# ChessPCB.net
KiCad netlist of a schematic drawn in EAGLE
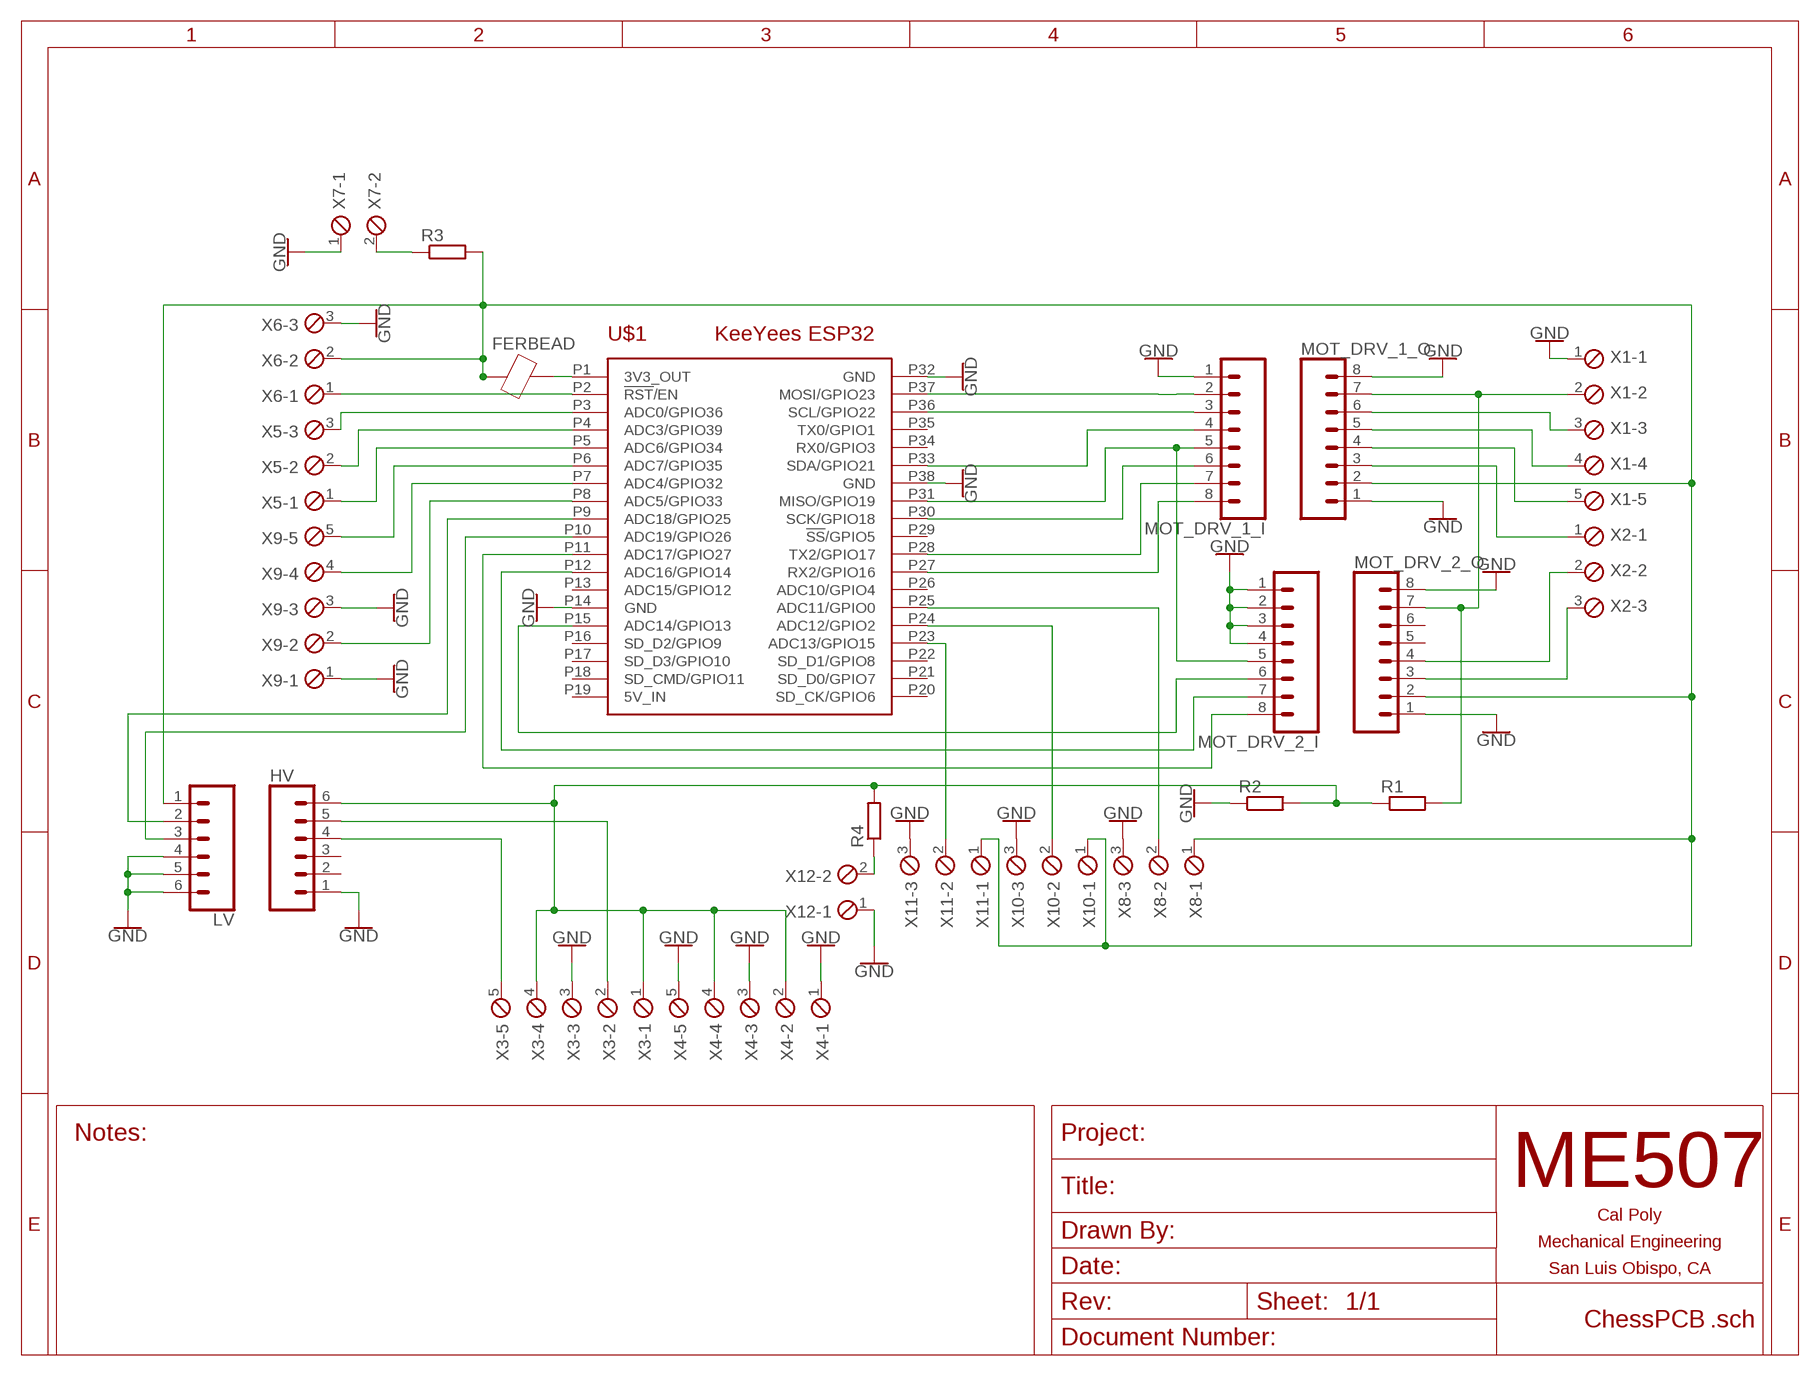
[diagram p0: schematic, sheet 1]

(export (version "E")
  (design (tool "Eeschema 10.0.6"))
  (components
    (comp (ref "FERBEAD")
      (value "BEAD0402")
      (footprint "eagle-import:0402")
      (libsource (lib "eagle-import") (part "BEAD0402"))
    )
    (comp (ref "HV")
      (value "CONN_06SILK_FEMALE_PTH")
      (footprint "eagle-import:1X06")
      (libsource (lib "eagle-import") (part "CONN_06SILK_FEMALE_PTH"))
    )
    (comp (ref "LV")
      (value "CONN_06SILK_FEMALE_PTH")
      (footprint "eagle-import:1X06")
      (libsource (lib "eagle-import") (part "CONN_06SILK_FEMALE_PTH"))
    )
    (comp (ref "MOT_DRV_1_I")
      (value "CONN_08\"")
      (footprint "eagle-import:1X08")
      (libsource (lib "eagle-import") (part "CONN_08{dblquote}"))
    )
    (comp (ref "MOT_DRV_1_O")
      (value "CONN_08\"")
      (footprint "eagle-import:1X08")
      (libsource (lib "eagle-import") (part "CONN_08{dblquote}"))
    )
    (comp (ref "MOT_DRV_2_I")
      (value "CONN_08\"")
      (footprint "eagle-import:1X08")
      (libsource (lib "eagle-import") (part "CONN_08{dblquote}"))
    )
    (comp (ref "MOT_DRV_2_O")
      (value "CONN_08\"")
      (footprint "eagle-import:1X08")
      (libsource (lib "eagle-import") (part "CONN_08{dblquote}"))
    )
    (comp (ref "R1")
      (value "R-EU_0204/7")
      (footprint "eagle-import:0204_7")
      (libsource (lib "eagle-import") (part "R-EU_0204/7"))
    )
    (comp (ref "R2")
      (value "R-EU_0204/7")
      (footprint "eagle-import:0204_7")
      (libsource (lib "eagle-import") (part "R-EU_0204/7"))
    )
    (comp (ref "R3")
      (value "R-EU_0204/7")
      (footprint "eagle-import:0204_7")
      (libsource (lib "eagle-import") (part "R-EU_0204/7"))
    )
    (comp (ref "R4")
      (value "R-EU_0204/7")
      (footprint "eagle-import:0204_7")
      (libsource (lib "eagle-import") (part "R-EU_0204/7"))
    )
    (comp (ref "U$1")
      (value "KEEYEES_ESP32")
      (footprint "eagle-import:KEEYEES_ESP32")
      (libsource (lib "eagle-import") (part "KEEYEES_ESP32"))
    )
    (comp (ref "X1")
      (value "SCREWTERM_5P_254")
      (footprint "eagle-import:5POL254")
      (libsource (lib "eagle-import") (part "SCREWTERM_5P_254"))
    )
    (comp (ref "X2")
      (value "SCREWTERM_3P_254")
      (footprint "eagle-import:3POL254")
      (libsource (lib "eagle-import") (part "SCREWTERM_3P_254"))
    )
    (comp (ref "X3")
      (value "SCREWTERM_5P_254")
      (footprint "eagle-import:5POL254")
      (libsource (lib "eagle-import") (part "SCREWTERM_5P_254"))
    )
    (comp (ref "X4")
      (value "SCREWTERM_5P_254")
      (footprint "eagle-import:5POL254")
      (libsource (lib "eagle-import") (part "SCREWTERM_5P_254"))
    )
    (comp (ref "X5")
      (value "SCREWTERM_3P_254")
      (footprint "eagle-import:3POL254")
      (libsource (lib "eagle-import") (part "SCREWTERM_3P_254"))
    )
    (comp (ref "X6")
      (value "SCREWTERM_3P_254")
      (footprint "eagle-import:3POL254")
      (libsource (lib "eagle-import") (part "SCREWTERM_3P_254"))
    )
    (comp (ref "X7")
      (value "SCREWTERM_2P_254")
      (footprint "eagle-import:2POL254")
      (libsource (lib "eagle-import") (part "SCREWTERM_2P_254"))
    )
    (comp (ref "X8")
      (value "SCREWTERM_3P_254")
      (footprint "eagle-import:3POL254")
      (libsource (lib "eagle-import") (part "SCREWTERM_3P_254"))
    )
    (comp (ref "X9")
      (value "SCREWTERM_5P_254")
      (footprint "eagle-import:5POL254")
      (libsource (lib "eagle-import") (part "SCREWTERM_5P_254"))
    )
    (comp (ref "X10")
      (value "SCREWTERM_3P_254")
      (footprint "eagle-import:3POL254")
      (libsource (lib "eagle-import") (part "SCREWTERM_3P_254"))
    )
    (comp (ref "X11")
      (value "SCREWTERM_3P_254")
      (footprint "eagle-import:3POL254")
      (libsource (lib "eagle-import") (part "SCREWTERM_3P_254"))
    )
    (comp (ref "X12")
      (value "SCREWTERM_2P_254")
      (footprint "eagle-import:2POL254")
      (libsource (lib "eagle-import") (part "SCREWTERM_2P_254"))
    )
  )
  (nets
    (net (code "1") (name "/5V_IN") (class "Default")
      (node (ref "U$1") (pin "P19") (pinfunction "5V_IN_P19") (pintype "power_in"))
    )
    (net (code "2") (name "GND") (class "Default")
      (node (ref "HV") (pin "1") (pinfunction "1_1") (pintype "passive"))
      (node (ref "LV") (pin "4") (pinfunction "4_4") (pintype "passive"))
      (node (ref "LV") (pin "5") (pinfunction "5_5") (pintype "passive"))
      (node (ref "LV") (pin "6") (pinfunction "6_6") (pintype "passive"))
      (node (ref "MOT_DRV_1_I") (pin "1") (pinfunction "1_1") (pintype "passive"))
      (node (ref "MOT_DRV_1_O") (pin "1") (pinfunction "1_1") (pintype "passive"))
      (node (ref "MOT_DRV_1_O") (pin "8") (pinfunction "8_8") (pintype "passive"))
      (node (ref "MOT_DRV_2_I") (pin "1") (pinfunction "1_1") (pintype "passive"))
      (node (ref "MOT_DRV_2_I") (pin "2") (pinfunction "2_2") (pintype "passive"))
      (node (ref "MOT_DRV_2_I") (pin "3") (pinfunction "3_3") (pintype "passive"))
      (node (ref "MOT_DRV_2_I") (pin "4") (pinfunction "4_4") (pintype "passive"))
      (node (ref "MOT_DRV_2_O") (pin "1") (pinfunction "1_1") (pintype "passive"))
      (node (ref "MOT_DRV_2_O") (pin "8") (pinfunction "8_8") (pintype "passive"))
      (node (ref "R2") (pin "1") (pinfunction "1_1") (pintype "passive"))
      (node (ref "U$1") (pin "P14") (pinfunction "GND_P14") (pintype "power_in"))
      (node (ref "U$1") (pin "P32") (pinfunction "GND_P32") (pintype "power_in"))
      (node (ref "U$1") (pin "P38") (pinfunction "GND_P38") (pintype "power_in"))
      (node (ref "X1") (pin "1") (pinfunction "1_1") (pintype "passive"))
      (node (ref "X10") (pin "3") (pinfunction "1_3") (pintype "passive"))
      (node (ref "X11") (pin "3") (pinfunction "1_3") (pintype "passive"))
      (node (ref "X12") (pin "1") (pinfunction "1_1") (pintype "passive"))
      (node (ref "X3") (pin "3") (pinfunction "1_3") (pintype "passive"))
      (node (ref "X4") (pin "1") (pinfunction "1_1") (pintype "passive"))
      (node (ref "X4") (pin "3") (pinfunction "1_3") (pintype "passive"))
      (node (ref "X4") (pin "5") (pinfunction "1_5") (pintype "passive"))
      (node (ref "X6") (pin "3") (pinfunction "1_3") (pintype "passive"))
      (node (ref "X7") (pin "1") (pinfunction "1_1") (pintype "passive"))
      (node (ref "X8") (pin "3") (pinfunction "1_3") (pintype "passive"))
      (node (ref "X9") (pin "1") (pinfunction "1_1") (pintype "passive"))
      (node (ref "X9") (pin "3") (pinfunction "1_3") (pintype "passive"))
    )
    (net (code "3") (name "Net-(MOT_DRV_1_O-Pad3)") (class "Default")
      (node (ref "MOT_DRV_1_O") (pin "3") (pinfunction "3_3") (pintype "passive"))
      (node (ref "X2") (pin "1") (pinfunction "1_1") (pintype "passive"))
    )
    (net (code "4") (name "Net-(U$1-3V3_OUT)") (class "Default")
      (node (ref "FERBEAD") (pin "2") (pinfunction "2_2") (pintype "bidirectional"))
      (node (ref "U$1") (pin "P1") (pinfunction "3V3_OUT_P1") (pintype "power_in"))
    )
    (net (code "5") (name "Net-(U$1-ADC0{slash}GPIO36)") (class "Default")
      (node (ref "U$1") (pin "P3") (pinfunction "ADC0/GPIO36_P3") (pintype "bidirectional"))
      (node (ref "X5") (pin "3") (pinfunction "1_3") (pintype "passive"))
    )
    (net (code "6") (name "Net-(U$1-ADC3{slash}GPIO39)") (class "Default")
      (node (ref "U$1") (pin "P4") (pinfunction "ADC3/GPIO39_P4") (pintype "bidirectional"))
      (node (ref "X5") (pin "2") (pinfunction "1_2") (pintype "passive"))
    )
    (net (code "7") (name "Net-(U$1-ADC4{slash}GPIO32)") (class "Default")
      (node (ref "U$1") (pin "P7") (pinfunction "ADC4/GPIO32_P7") (pintype "bidirectional"))
      (node (ref "X9") (pin "4") (pinfunction "1_4") (pintype "passive"))
    )
    (net (code "8") (name "Net-(U$1-ADC5{slash}GPIO33)") (class "Default")
      (node (ref "U$1") (pin "P8") (pinfunction "ADC5/GPIO33_P8") (pintype "bidirectional"))
      (node (ref "X9") (pin "2") (pinfunction "1_2") (pintype "passive"))
    )
    (net (code "9") (name "Net-(U$1-ADC6{slash}GPIO34)") (class "Default")
      (node (ref "U$1") (pin "P5") (pinfunction "ADC6/GPIO34_P5") (pintype "bidirectional"))
      (node (ref "X5") (pin "1") (pinfunction "1_1") (pintype "passive"))
    )
    (net (code "10") (name "Net-(U$1-ADC7{slash}GPIO35)") (class "Default")
      (node (ref "U$1") (pin "P6") (pinfunction "ADC7/GPIO35_P6") (pintype "bidirectional"))
      (node (ref "X9") (pin "5") (pinfunction "1_5") (pintype "passive"))
    )
    (net (code "11") (name "Net-(U$1-ADC11{slash}GPIO0)") (class "Default")
      (node (ref "U$1") (pin "P25") (pinfunction "ADC11/GPIO0_P25") (pintype "bidirectional"))
      (node (ref "X8") (pin "2") (pinfunction "1_2") (pintype "passive"))
    )
    (net (code "12") (name "Net-(U$1-ADC12{slash}GPIO2)") (class "Default")
      (node (ref "U$1") (pin "P24") (pinfunction "ADC12/GPIO2_P24") (pintype "bidirectional"))
      (node (ref "X10") (pin "2") (pinfunction "1_2") (pintype "passive"))
    )
    (net (code "13") (name "Net-(U$1-ADC13{slash}GPIO15)") (class "Default")
      (node (ref "U$1") (pin "P23") (pinfunction "ADC13/GPIO15_P23") (pintype "bidirectional"))
      (node (ref "X11") (pin "2") (pinfunction "1_2") (pintype "passive"))
    )
    (net (code "14") (name "Net-(U$1-ADC14{slash}GPIO13)") (class "Default")
      (node (ref "MOT_DRV_2_I") (pin "6") (pinfunction "6_6") (pintype "passive"))
      (node (ref "U$1") (pin "P15") (pinfunction "ADC14/GPIO13_P15") (pintype "bidirectional"))
    )
    (net (code "15") (name "Net-(U$1-ADC16{slash}GPIO14)") (class "Default")
      (node (ref "MOT_DRV_2_I") (pin "7") (pinfunction "7_7") (pintype "passive"))
      (node (ref "U$1") (pin "P12") (pinfunction "ADC16/GPIO14_P12") (pintype "bidirectional"))
    )
    (net (code "16") (name "Net-(U$1-ADC17{slash}GPIO27)") (class "Default")
      (node (ref "MOT_DRV_2_I") (pin "8") (pinfunction "8_8") (pintype "passive"))
      (node (ref "U$1") (pin "P11") (pinfunction "ADC17/GPIO27_P11") (pintype "bidirectional"))
    )
    (net (code "17") (name "Net-(U$1-ADC18{slash}GPIO25)") (class "Default")
      (node (ref "LV") (pin "2") (pinfunction "2_2") (pintype "passive"))
      (node (ref "U$1") (pin "P9") (pinfunction "ADC18/GPIO25_P9") (pintype "bidirectional"))
    )
    (net (code "18") (name "Net-(U$1-ADC19{slash}GPIO26)") (class "Default")
      (node (ref "LV") (pin "3") (pinfunction "3_3") (pintype "passive"))
      (node (ref "U$1") (pin "P10") (pinfunction "ADC19/GPIO26_P10") (pintype "bidirectional"))
    )
    (net (code "19") (name "Net-(U$1-MISO{slash}GPIO19)") (class "Default")
      (node (ref "MOT_DRV_1_I") (pin "5") (pinfunction "5_5") (pintype "passive"))
      (node (ref "MOT_DRV_2_I") (pin "5") (pinfunction "5_5") (pintype "passive"))
      (node (ref "U$1") (pin "P31") (pinfunction "MISO/GPIO19_P31") (pintype "bidirectional"))
    )
    (net (code "20") (name "Net-(U$1-MOSI{slash}GPIO23)") (class "Default")
      (node (ref "MOT_DRV_1_I") (pin "2") (pinfunction "2_2") (pintype "passive"))
      (node (ref "U$1") (pin "P37") (pinfunction "MOSI/GPIO23_P37") (pintype "bidirectional"))
    )
    (net (code "21") (name "Net-(U$1-RX2{slash}GPIO16)") (class "Default")
      (node (ref "MOT_DRV_1_I") (pin "8") (pinfunction "8_8") (pintype "passive"))
      (node (ref "U$1") (pin "P27") (pinfunction "RX2/GPIO16_P27") (pintype "bidirectional"))
    )
    (net (code "22") (name "Net-(U$1-SCK{slash}GPIO18)") (class "Default")
      (node (ref "MOT_DRV_1_I") (pin "6") (pinfunction "6_6") (pintype "passive"))
      (node (ref "U$1") (pin "P30") (pinfunction "SCK/GPIO18_P30") (pintype "bidirectional"))
    )
    (net (code "23") (name "Net-(U$1-SCL{slash}GPIO22)") (class "Default")
      (node (ref "MOT_DRV_1_I") (pin "3") (pinfunction "3_3") (pintype "passive"))
      (node (ref "U$1") (pin "P36") (pinfunction "SCL/GPIO22_P36") (pintype "bidirectional"))
    )
    (net (code "24") (name "Net-(U$1-SDA{slash}GPIO21)") (class "Default")
      (node (ref "MOT_DRV_1_I") (pin "4") (pinfunction "4_4") (pintype "passive"))
      (node (ref "U$1") (pin "P33") (pinfunction "SDA/GPIO21_P33") (pintype "bidirectional"))
    )
    (net (code "25") (name "Net-(U$1-TX2{slash}GPIO17)") (class "Default")
      (node (ref "MOT_DRV_1_I") (pin "7") (pinfunction "7_7") (pintype "passive"))
      (node (ref "U$1") (pin "P28") (pinfunction "TX2/GPIO17_P28") (pintype "bidirectional"))
    )
    (net (code "26") (name "Net-(U$1-~{RST}{slash}EN)") (class "Default")
      (node (ref "U$1") (pin "P2") (pinfunction "~{RST}/EN_P2") (pintype "input"))
      (node (ref "X6") (pin "1") (pinfunction "1_1") (pintype "passive"))
    )
    (net (code "27") (name "Net-(X1B-1)") (class "Default")
      (node (ref "MOT_DRV_1_O") (pin "7") (pinfunction "7_7") (pintype "passive"))
      (node (ref "MOT_DRV_2_O") (pin "7") (pinfunction "7_7") (pintype "passive"))
      (node (ref "R1") (pin "2") (pinfunction "2_2") (pintype "passive"))
      (node (ref "X1") (pin "2") (pinfunction "1_2") (pintype "passive"))
    )
    (net (code "28") (name "Net-(X1C-1)") (class "Default")
      (node (ref "MOT_DRV_1_O") (pin "6") (pinfunction "6_6") (pintype "passive"))
      (node (ref "X1") (pin "3") (pinfunction "1_3") (pintype "passive"))
    )
    (net (code "29") (name "Net-(X1D-1)") (class "Default")
      (node (ref "MOT_DRV_1_O") (pin "5") (pinfunction "5_5") (pintype "passive"))
      (node (ref "X1") (pin "4") (pinfunction "1_4") (pintype "passive"))
    )
    (net (code "30") (name "Net-(X1E-1)") (class "Default")
      (node (ref "MOT_DRV_1_O") (pin "4") (pinfunction "4_4") (pintype "passive"))
      (node (ref "X1") (pin "5") (pinfunction "1_5") (pintype "passive"))
    )
    (net (code "31") (name "Net-(X2B-1)") (class "Default")
      (node (ref "MOT_DRV_2_O") (pin "4") (pinfunction "4_4") (pintype "passive"))
      (node (ref "X2") (pin "2") (pinfunction "1_2") (pintype "passive"))
    )
    (net (code "32") (name "Net-(X2C-1)") (class "Default")
      (node (ref "MOT_DRV_2_O") (pin "3") (pinfunction "3_3") (pintype "passive"))
      (node (ref "X2") (pin "3") (pinfunction "1_3") (pintype "passive"))
    )
    (net (code "33") (name "Net-(X3B-1)") (class "Default")
      (node (ref "HV") (pin "5") (pinfunction "5_5") (pintype "passive"))
      (node (ref "X3") (pin "2") (pinfunction "1_2") (pintype "passive"))
    )
    (net (code "34") (name "Net-(X3D-1)") (class "Default")
      (node (ref "HV") (pin "6") (pinfunction "6_6") (pintype "passive"))
      (node (ref "R1") (pin "1") (pinfunction "1_1") (pintype "passive"))
      (node (ref "R2") (pin "2") (pinfunction "2_2") (pintype "passive"))
      (node (ref "R4") (pin "2") (pinfunction "2_2") (pintype "passive"))
      (node (ref "X3") (pin "1") (pinfunction "1_1") (pintype "passive"))
      (node (ref "X3") (pin "4") (pinfunction "1_4") (pintype "passive"))
      (node (ref "X4") (pin "2") (pinfunction "1_2") (pintype "passive"))
      (node (ref "X4") (pin "4") (pinfunction "1_4") (pintype "passive"))
    )
    (net (code "35") (name "Net-(X3E-1)") (class "Default")
      (node (ref "HV") (pin "4") (pinfunction "4_4") (pintype "passive"))
      (node (ref "X3") (pin "5") (pinfunction "1_5") (pintype "passive"))
    )
    (net (code "36") (name "Net-(X6B-1)") (class "Default")
      (node (ref "FERBEAD") (pin "1") (pinfunction "1_1") (pintype "bidirectional"))
      (node (ref "LV") (pin "1") (pinfunction "1_1") (pintype "passive"))
      (node (ref "MOT_DRV_1_O") (pin "2") (pinfunction "2_2") (pintype "passive"))
      (node (ref "MOT_DRV_2_O") (pin "2") (pinfunction "2_2") (pintype "passive"))
      (node (ref "R3") (pin "2") (pinfunction "2_2") (pintype "passive"))
      (node (ref "X10") (pin "1") (pinfunction "1_1") (pintype "passive"))
      (node (ref "X11") (pin "1") (pinfunction "1_1") (pintype "passive"))
      (node (ref "X6") (pin "2") (pinfunction "1_2") (pintype "passive"))
      (node (ref "X8") (pin "1") (pinfunction "1_1") (pintype "passive"))
    )
    (net (code "37") (name "Net-(X7B-1)") (class "Default")
      (node (ref "R3") (pin "1") (pinfunction "1_1") (pintype "passive"))
      (node (ref "X7") (pin "2") (pinfunction "1_2") (pintype "passive"))
    )
    (net (code "38") (name "Net-(X12B-1)") (class "Default")
      (node (ref "R4") (pin "1") (pinfunction "1_1") (pintype "passive"))
      (node (ref "X12") (pin "2") (pinfunction "1_2") (pintype "passive"))
    )
    (net (code "39") (name "unconnected-(HV-Pad2)") (class "Default")
      (node (ref "HV") (pin "2") (pinfunction "2_2") (pintype "passive"))
    )
    (net (code "40") (name "unconnected-(HV-Pad3)") (class "Default")
      (node (ref "HV") (pin "3") (pinfunction "3_3") (pintype "passive"))
    )
    (net (code "41") (name "unconnected-(MOT_DRV_2_O-Pad5)") (class "Default")
      (node (ref "MOT_DRV_2_O") (pin "5") (pinfunction "5_5") (pintype "passive"))
    )
    (net (code "42") (name "unconnected-(MOT_DRV_2_O-Pad6)") (class "Default")
      (node (ref "MOT_DRV_2_O") (pin "6") (pinfunction "6_6") (pintype "passive"))
    )
    (net (code "43") (name "unconnected-(U$1-ADC10{slash}GPIO4-PadP26)") (class "Default")
      (node (ref "U$1") (pin "P26") (pinfunction "ADC10/GPIO4_P26") (pintype "bidirectional"))
    )
    (net (code "44") (name "unconnected-(U$1-ADC15{slash}GPIO12-PadP13)") (class "Default")
      (node (ref "U$1") (pin "P13") (pinfunction "ADC15/GPIO12_P13") (pintype "bidirectional"))
    )
    (net (code "45") (name "unconnected-(U$1-RX0{slash}GPIO3-PadP34)") (class "Default")
      (node (ref "U$1") (pin "P34") (pinfunction "RX0/GPIO3_P34") (pintype "bidirectional"))
    )
    (net (code "46") (name "unconnected-(U$1-SD_CK{slash}GPIO6-PadP20)") (class "Default")
      (node (ref "U$1") (pin "P20") (pinfunction "SD_CK/GPIO6_P20") (pintype "bidirectional"))
    )
    (net (code "47") (name "unconnected-(U$1-SD_CMD{slash}GPIO11-PadP18)") (class "Default")
      (node (ref "U$1") (pin "P18") (pinfunction "SD_CMD/GPIO11_P18") (pintype "bidirectional"))
    )
    (net (code "48") (name "unconnected-(U$1-SD_D0{slash}GPIO7-PadP21)") (class "Default")
      (node (ref "U$1") (pin "P21") (pinfunction "SD_D0/GPIO7_P21") (pintype "bidirectional"))
    )
    (net (code "49") (name "unconnected-(U$1-SD_D1{slash}GPIO8-PadP22)") (class "Default")
      (node (ref "U$1") (pin "P22") (pinfunction "SD_D1/GPIO8_P22") (pintype "bidirectional"))
    )
    (net (code "50") (name "unconnected-(U$1-SD_D2{slash}GPIO9-PadP16)") (class "Default")
      (node (ref "U$1") (pin "P16") (pinfunction "SD_D2/GPIO9_P16") (pintype "bidirectional"))
    )
    (net (code "51") (name "unconnected-(U$1-SD_D3{slash}GPIO10-PadP17)") (class "Default")
      (node (ref "U$1") (pin "P17") (pinfunction "SD_D3/GPIO10_P17") (pintype "bidirectional"))
    )
    (net (code "52") (name "unconnected-(U$1-TX0{slash}GPIO1-PadP35)") (class "Default")
      (node (ref "U$1") (pin "P35") (pinfunction "TX0/GPIO1_P35") (pintype "bidirectional"))
    )
    (net (code "53") (name "unconnected-(U$1-~{SS}{slash}GPIO5-PadP29)") (class "Default")
      (node (ref "U$1") (pin "P29") (pinfunction "~{SS}/GPIO5_P29") (pintype "bidirectional"))
    )
  )
)
